# Display.net
KiCad netlist of a schematic drawn in Altium Designer
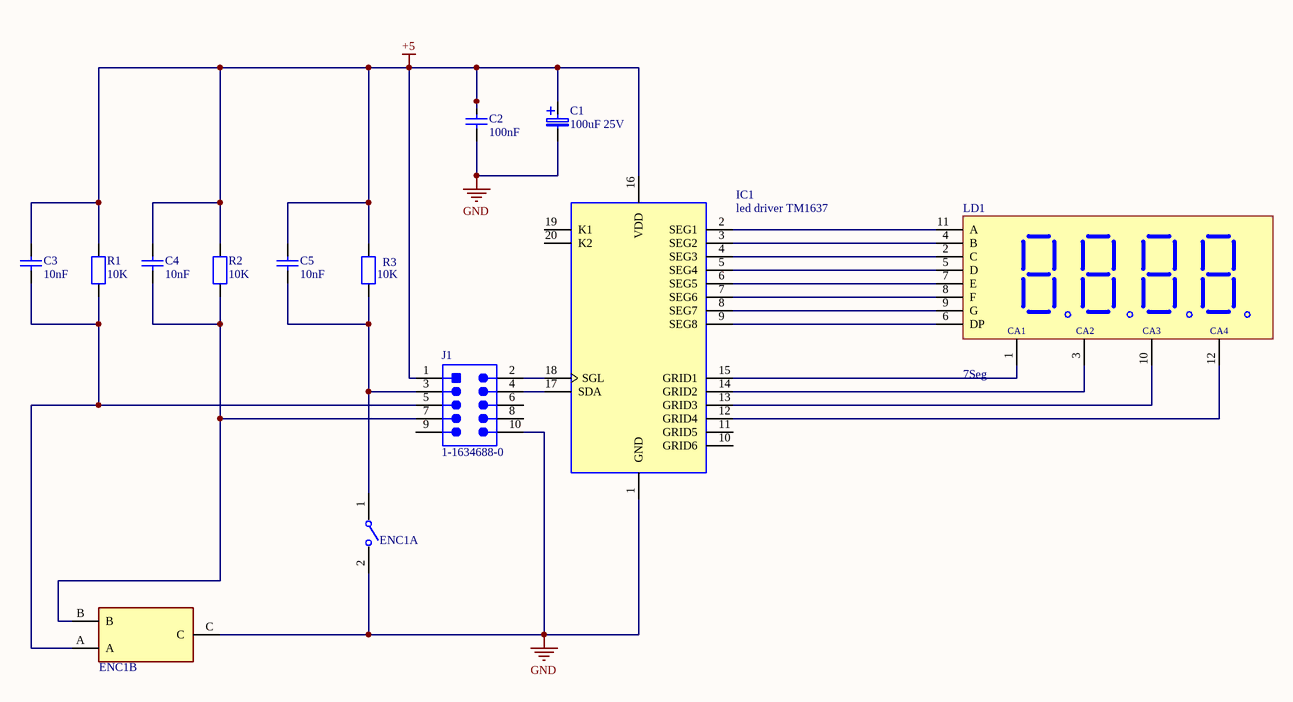
[diagram p0: Display.SchDoc]

(export (version "E")
  (design (tool "Eeschema 10.0.6"))
  (components
    (comp (ref "C1")
      (value "100uF 25V")
      (footprint "TAP106M050BRW")
      (description "Tantalum Capacitors - Solid Leaded 50V 10uF 20% ESR=1.6 Ohm TAP106M050BRW")
      (fields
        (field (name "MOUSER PART NUMBER") "581-TAP106M050BRW")
        (field (name "MANUFACTURER_PART_NUMBER") "TAP106M050BRW")
      )
      (libsource (lib "displaySolderstation") (part "capacitor THT radial tantalum"))
    )
    (comp (ref "C2")
      (value "100nF")
      (footprint "CAPC2012X88N")
      (fields (field (name "MANUFACTURER") "Kemet") (field (name "PART NUMBER") "C0402C104K4RACTU"))
      (libsource (lib "displaySolderstation") (part "Capacitor ceramic 0805"))
    )
    (comp (ref "C3")
      (value "10nF")
      (footprint "CAPC2012X88N")
      (fields (field (name "MANUFACTURER") "Kemet") (field (name "PART NUMBER") "C0402C104K4RACTU"))
      (libsource (lib "displaySolderstation") (part "Capacitor ceramic 0805"))
    )
    (comp (ref "C4")
      (value "10nF")
      (footprint "CAPC2012X88N")
      (fields (field (name "MANUFACTURER") "Kemet") (field (name "PART NUMBER") "C0402C104K4RACTU"))
      (libsource (lib "displaySolderstation") (part "Capacitor ceramic 0805"))
    )
    (comp (ref "C5")
      (value "10nF")
      (footprint "CAPC2012X88N")
      (fields (field (name "MANUFACTURER") "Kemet") (field (name "PART NUMBER") "C0402C104K4RACTU"))
      (libsource (lib "displaySolderstation") (part "Capacitor ceramic 0805"))
    )
    (comp (ref "ENC1")
      (value "PEC11R-4220F-S0012")
      (footprint "PEC11R_4220F_S0012")
      (description "ROTARY ENCODER MECHANICAL 12PPR PEC11R-4220F-S0012")
      (libsource (lib "displaySolderstation") (part "RotEncoderButtom"))
    )
    (comp (ref "IC1")
      (value "led driver TM1637")
      (footprint "N-20")
      (description "LED Drive Control Special Circuit")
      (fields (field (name "MF") "Titan Micro Electronics") (field (name "MP") "TM1637"))
      (libsource (lib "displaySolderstation") (part "led driver TM1637"))
    )
    (comp (ref "J1")
      (value "1-1634688-0")
      (footprint "TECO-1-1634688-0-10_V")
      (fields (field (name "MANUFACTURER") "TE Connectivity"))
      (libsource (lib "displaySolderstation") (part "pin header 2X5 10pins"))
    )
    (comp (ref "LD1")
      (value "7Seg")
      (footprint "KW4-801AVB/KW4-801CVB")
      (description "4-Digit LED Display TME KW4-801AVB")
      (libsource (lib "displaySolderstation") (part "Display LED 4-Digit"))
    )
    (comp (ref "R1")
      (value "10K")
      (footprint "RESC2012X50N")
      (fields (field (name "MANUFACTURER") "Vishay Dale") (field (name "PART NUMBER") "CRCW08050000Z0EA"))
      (libsource (lib "displaySolderstation") (part "resistor 0805"))
    )
    (comp (ref "R2")
      (value "10K")
      (footprint "RESC2012X50N")
      (fields (field (name "MANUFACTURER") "Vishay Dale") (field (name "PART NUMBER") "CRCW08050000Z0EA"))
      (libsource (lib "displaySolderstation") (part "resistor 0805"))
    )
    (comp (ref "R3")
      (value "10K")
      (footprint "RESC2012X50N")
      (fields (field (name "MANUFACTURER") "Vishay Dale") (field (name "PART NUMBER") "CRCW08050000Z0EA"))
      (libsource (lib "displaySolderstation") (part "resistor 0805"))
    )
  )
  (nets
    (net (code "1") (name "+5") (class "Default")
      (node (ref "C1") (pin "1") (pinfunction "1_1") (pintype "passive"))
      (node (ref "C2") (pin "2") (pinfunction "2_2") (pintype "passive"))
      (node (ref "C3") (pin "2") (pinfunction "2_2") (pintype "passive"))
      (node (ref "C4") (pin "2") (pinfunction "2_2") (pintype "passive"))
      (node (ref "C5") (pin "2") (pinfunction "2_2") (pintype "passive"))
      (node (ref "IC1") (pin "16") (pinfunction "VDD_16") (pintype "power_in"))
      (node (ref "J1") (pin "1") (pinfunction "1_1") (pintype "passive"))
      (node (ref "R1") (pin "2") (pinfunction "2_2") (pintype "passive"))
      (node (ref "R2") (pin "2") (pinfunction "2_2") (pintype "passive"))
      (node (ref "R3") (pin "2") (pinfunction "2_2") (pintype "passive"))
    )
    (net (code "2") (name "GND") (class "Default")
      (node (ref "C1") (pin "2") (pinfunction "2_2") (pintype "passive"))
      (node (ref "C2") (pin "1") (pinfunction "1_1") (pintype "passive"))
      (node (ref "ENC1") (pin "2") (pinfunction "2_2") (pintype "passive"))
      (node (ref "ENC1") (pin "C") (pinfunction "C_C") (pintype "passive"))
      (node (ref "IC1") (pin "1") (pinfunction "GND_1") (pintype "power_in"))
      (node (ref "J1") (pin "10") (pinfunction "10_10") (pintype "passive"))
    )
    (net (code "3") (name "Net-(C3-Pad1)") (class "Default")
      (node (ref "C3") (pin "1") (pinfunction "1_1") (pintype "passive"))
      (node (ref "ENC1") (pin "A") (pinfunction "A_A") (pintype "passive"))
      (node (ref "J1") (pin "5") (pinfunction "5_5") (pintype "passive"))
      (node (ref "R1") (pin "1") (pinfunction "1_1") (pintype "passive"))
    )
    (net (code "4") (name "Net-(C4-Pad1)") (class "Default")
      (node (ref "C4") (pin "1") (pinfunction "1_1") (pintype "passive"))
      (node (ref "ENC1") (pin "B") (pinfunction "B_B") (pintype "passive"))
      (node (ref "J1") (pin "7") (pinfunction "7_7") (pintype "passive"))
      (node (ref "R2") (pin "1") (pinfunction "1_1") (pintype "passive"))
    )
    (net (code "5") (name "Net-(C5-Pad1)") (class "Default")
      (node (ref "C5") (pin "1") (pinfunction "1_1") (pintype "passive"))
      (node (ref "ENC1") (pin "1") (pinfunction "1_1") (pintype "passive"))
      (node (ref "J1") (pin "3") (pinfunction "3_3") (pintype "passive"))
      (node (ref "R3") (pin "1") (pinfunction "1_1") (pintype "passive"))
    )
    (net (code "6") (name "Net-(IC1-GRID1)") (class "Default")
      (node (ref "IC1") (pin "15") (pinfunction "GRID1_15") (pintype "passive"))
      (node (ref "LD1") (pin "1") (pinfunction "CA1_1") (pintype "passive"))
    )
    (net (code "7") (name "Net-(IC1-GRID2)") (class "Default")
      (node (ref "IC1") (pin "14") (pinfunction "GRID2_14") (pintype "passive"))
      (node (ref "LD1") (pin "3") (pinfunction "13_3") (pintype "passive"))
    )
    (net (code "8") (name "Net-(IC1-GRID3)") (class "Default")
      (node (ref "IC1") (pin "13") (pinfunction "GRID3_13") (pintype "passive"))
      (node (ref "LD1") (pin "10") (pinfunction "14_10") (pintype "passive"))
    )
    (net (code "9") (name "Net-(IC1-GRID4)") (class "Default")
      (node (ref "IC1") (pin "12") (pinfunction "GRID4_12") (pintype "passive"))
      (node (ref "LD1") (pin "12") (pinfunction "15_12") (pintype "passive"))
    )
    (net (code "10") (name "Net-(IC1-SDA)") (class "Default")
      (node (ref "IC1") (pin "17") (pinfunction "SDA_17") (pintype "passive"))
      (node (ref "J1") (pin "4") (pinfunction "4_4") (pintype "passive"))
    )
    (net (code "11") (name "Net-(IC1-SEG1)") (class "Default")
      (node (ref "IC1") (pin "2") (pinfunction "SEG1_2") (pintype "passive"))
      (node (ref "LD1") (pin "11") (pinfunction "A_11") (pintype "passive"))
    )
    (net (code "12") (name "Net-(IC1-SEG2)") (class "Default")
      (node (ref "IC1") (pin "3") (pinfunction "SEG2_3") (pintype "passive"))
      (node (ref "LD1") (pin "4") (pinfunction "B_4") (pintype "passive"))
    )
    (net (code "13") (name "Net-(IC1-SEG3)") (class "Default")
      (node (ref "IC1") (pin "4") (pinfunction "SEG3_4") (pintype "passive"))
      (node (ref "LD1") (pin "2") (pinfunction "C_2") (pintype "passive"))
    )
    (net (code "14") (name "Net-(IC1-SEG4)") (class "Default")
      (node (ref "IC1") (pin "5") (pinfunction "SEG4_5") (pintype "passive"))
      (node (ref "LD1") (pin "5") (pinfunction "D_5") (pintype "passive"))
    )
    (net (code "15") (name "Net-(IC1-SEG5)") (class "Default")
      (node (ref "IC1") (pin "6") (pinfunction "SEG5_6") (pintype "passive"))
      (node (ref "LD1") (pin "7") (pinfunction "E_7") (pintype "passive"))
    )
    (net (code "16") (name "Net-(IC1-SEG6)") (class "Default")
      (node (ref "IC1") (pin "7") (pinfunction "SEG6_7") (pintype "passive"))
      (node (ref "LD1") (pin "8") (pinfunction "F_8") (pintype "passive"))
    )
    (net (code "17") (name "Net-(IC1-SEG7)") (class "Default")
      (node (ref "IC1") (pin "8") (pinfunction "SEG7_8") (pintype "passive"))
      (node (ref "LD1") (pin "9") (pinfunction "G_9") (pintype "passive"))
    )
    (net (code "18") (name "Net-(IC1-SEG8)") (class "Default")
      (node (ref "IC1") (pin "9") (pinfunction "SEG8_9") (pintype "passive"))
      (node (ref "LD1") (pin "6") (pinfunction "DP_6") (pintype "passive"))
    )
    (net (code "19") (name "Net-(IC1-SGL)") (class "Default")
      (node (ref "IC1") (pin "18") (pinfunction "SGL_18") (pintype "passive"))
      (node (ref "J1") (pin "2") (pinfunction "2_2") (pintype "passive"))
    )
    (net (code "20") (name "unconnected-(IC1-GRID5-Pad11)") (class "Default")
      (node (ref "IC1") (pin "11") (pinfunction "GRID5_11") (pintype "passive"))
    )
    (net (code "21") (name "unconnected-(IC1-GRID6-Pad10)") (class "Default")
      (node (ref "IC1") (pin "10") (pinfunction "GRID6_10") (pintype "passive"))
    )
    (net (code "22") (name "unconnected-(IC1-K1-Pad19)") (class "Default")
      (node (ref "IC1") (pin "19") (pinfunction "K1_19") (pintype "passive"))
    )
    (net (code "23") (name "unconnected-(IC1-K2-Pad20)") (class "Default")
      (node (ref "IC1") (pin "20") (pinfunction "K2_20") (pintype "passive"))
    )
    (net (code "24") (name "unconnected-(J1-Pad6)") (class "Default")
      (node (ref "J1") (pin "6") (pinfunction "6_6") (pintype "passive"))
    )
    (net (code "25") (name "unconnected-(J1-Pad8)") (class "Default")
      (node (ref "J1") (pin "8") (pinfunction "8_8") (pintype "passive"))
    )
    (net (code "26") (name "unconnected-(J1-Pad9)") (class "Default")
      (node (ref "J1") (pin "9") (pinfunction "9_9") (pintype "passive"))
    )
  )
)
